# 555-blinker.net
KiCad netlist of a schematic drawn in EAGLE
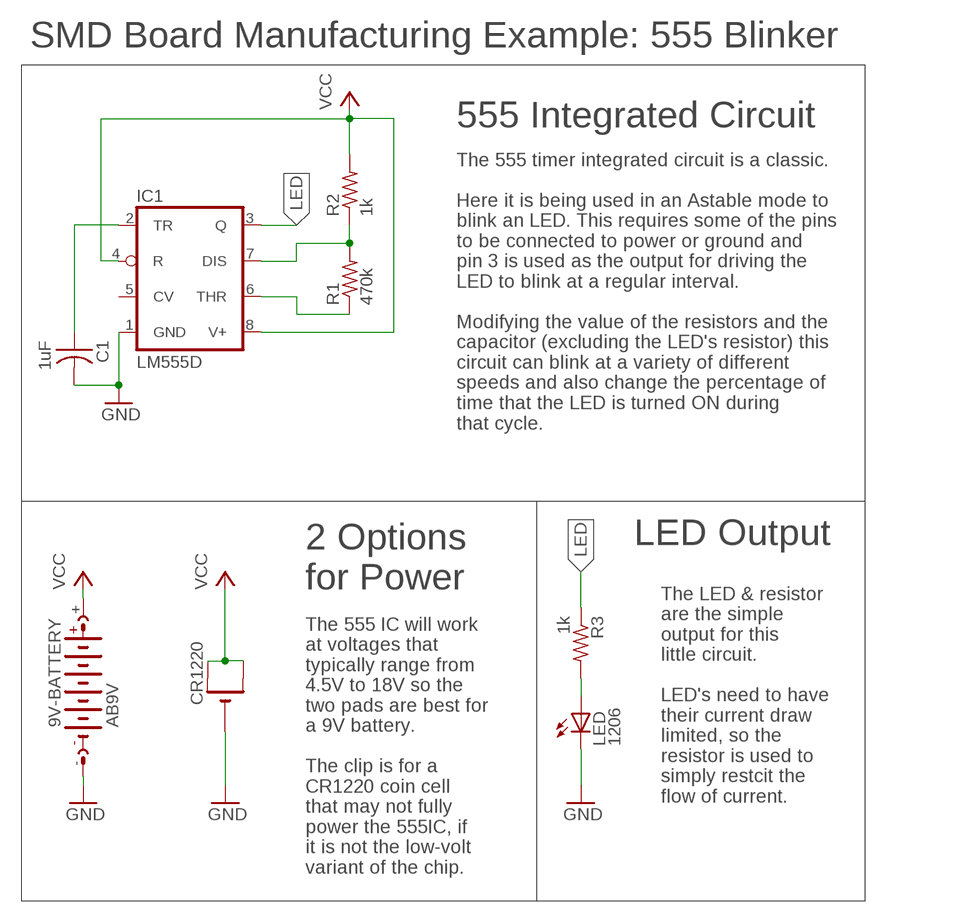
[diagram p0: schematic, sheet 1]

(export (version "E")
  (design (tool "Eeschema 10.0.6"))
  (components
    (comp (ref "9V-BATTERY")
      (value "AB9V")
      (footprint "eagle-import:AB9V")
      (libsource (lib "eagle-import") (part "AB9V"))
    )
    (comp (ref "C1")
      (value "1uF")
      (footprint "eagle-import:C1206FAB")
      (libsource (lib "eagle-import") (part "CAP-US1206FAB"))
    )
    (comp (ref "CR1220")
      (value "CR1220SMT")
      (footprint "eagle-import:CR1220-SMD")
      (libsource (lib "eagle-import") (part "CR1220SMT"))
    )
    (comp (ref "IC1")
      (value "LM555D")
      (footprint "eagle-import:SO08")
      (libsource (lib "eagle-import") (part "555DLM"))
    )
    (comp (ref "LED")
      (value "1206")
      (footprint "eagle-import:LED1206FAB")
      (libsource (lib "eagle-import") (part "LEDFAB1206"))
    )
    (comp (ref "R1")
      (value "470k")
      (footprint "eagle-import:R1206FAB")
      (libsource (lib "eagle-import") (part "RES-US1206FAB"))
    )
    (comp (ref "R2")
      (value "1k")
      (footprint "eagle-import:R1206FAB")
      (libsource (lib "eagle-import") (part "RES-US1206FAB"))
    )
    (comp (ref "R3")
      (value "1k")
      (footprint "eagle-import:R1206FAB")
      (libsource (lib "eagle-import") (part "RES-US1206FAB"))
    )
  )
  (nets
    (net (code "1") (name "GND") (class "Default")
      (node (ref "9V-BATTERY") (pin "-") (pinfunction "-_-") (pintype "passive"))
      (node (ref "C1") (pin "2") (pinfunction "2_2") (pintype "passive"))
      (node (ref "CR1220") (pin "-") (pinfunction "-_-") (pintype "passive"))
      (node (ref "IC1") (pin "1") (pinfunction "GND_1") (pintype "power_in"))
      (node (ref "LED") (pin "2") (pinfunction "C_2") (pintype "passive"))
    )
    (net (code "2") (name "LED") (class "Default")
      (node (ref "IC1") (pin "3") (pinfunction "Q_3") (pintype "output"))
      (node (ref "R3") (pin "1") (pinfunction "1_1") (pintype "passive"))
    )
    (net (code "3") (name "Net-(IC1-DIS)") (class "Default")
      (node (ref "IC1") (pin "7") (pinfunction "DIS_7") (pintype "input"))
      (node (ref "R1") (pin "2") (pinfunction "2_2") (pintype "passive"))
      (node (ref "R2") (pin "1") (pinfunction "1_1") (pintype "passive"))
    )
    (net (code "4") (name "Net-(IC1-THR)") (class "Default")
      (node (ref "IC1") (pin "6") (pinfunction "THR_6") (pintype "input"))
      (node (ref "R1") (pin "1") (pinfunction "1_1") (pintype "passive"))
    )
    (net (code "5") (name "Net-(IC1-TR)") (class "Default")
      (node (ref "C1") (pin "1") (pinfunction "1_1") (pintype "passive"))
      (node (ref "IC1") (pin "2") (pinfunction "TR_2") (pintype "input"))
    )
    (net (code "6") (name "Net-(LED-A)") (class "Default")
      (node (ref "LED") (pin "1") (pinfunction "A_1") (pintype "passive"))
      (node (ref "R3") (pin "2") (pinfunction "2_2") (pintype "passive"))
    )
    (net (code "7") (name "VCC") (class "Default")
      (node (ref "9V-BATTERY") (pin "+") (pinfunction "+_+") (pintype "passive"))
      (node (ref "CR1220") (pin "+$1") (pinfunction "+_+$1") (pintype "passive"))
      (node (ref "CR1220") (pin "+$2") (pinfunction "+1_+$2") (pintype "passive"))
      (node (ref "IC1") (pin "4") (pinfunction "R_4") (pintype "input"))
      (node (ref "IC1") (pin "8") (pinfunction "V+_8") (pintype "power_in"))
      (node (ref "R2") (pin "2") (pinfunction "2_2") (pintype "passive"))
    )
    (net (code "8") (name "unconnected-(IC1-CV-Pad5)") (class "Default")
      (node (ref "IC1") (pin "5") (pinfunction "CV_5") (pintype "input"))
    )
  )
)
